# Sensor_MQ-135.net
KiCad netlist of a schematic drawn in Altium Designer
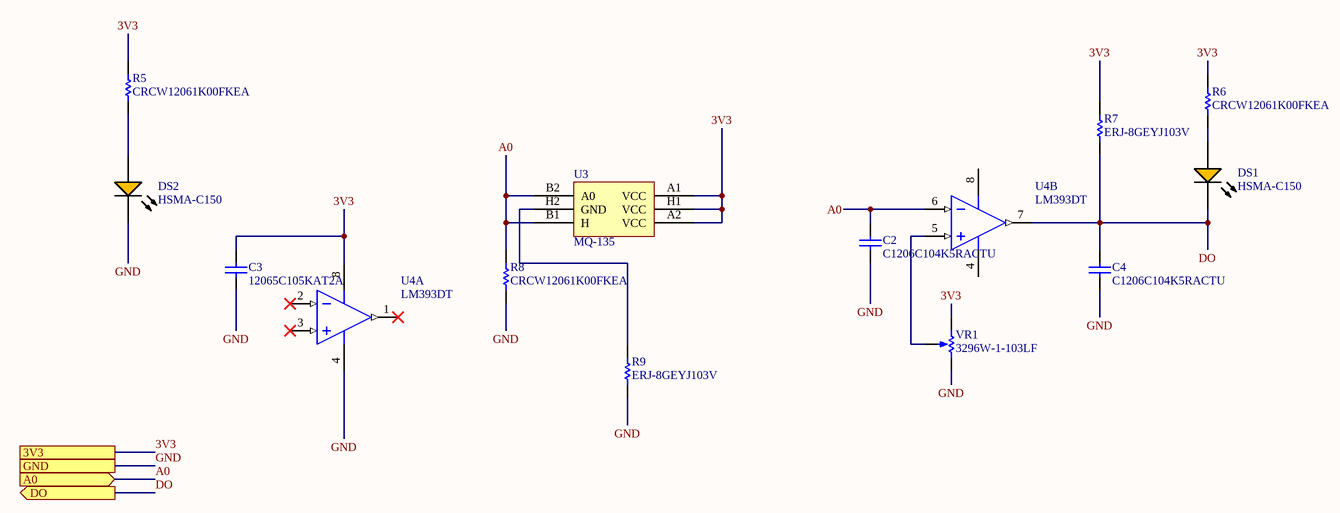
[diagram p0: Sensor_MQ-135.SchDoc]

(export (version "E")
  (design (tool "Eeschema 10.0.6"))
  (components
    (comp (ref "C2")
      (value "C1206C104K5RACTU")
      (footprint "KEMT-1206-2_M")
      (description "CAP, Ceramic, 0.1 uF, +/- 10%, 50 V, -55 to 125 degC, 1206 (3216 Metric), RoHS, Tape and Reel")
      (fields (field (name "MANUFACTURER") "Kemet"))
      (libsource (lib "Altium Content Vault") (part "CAP-NP-2"))
    )
    (comp (ref "C3")
      (value "12065C105KAT2A")
      (footprint "CAPC3216X180X50LL20T25")
      (description "Chip Capacitor, 1 uF, +/- 10%, 50 V, -55 to 125 degC, 1206 (3216 Metric), RoHS, Tape and Reel")
      (fields (field (name "MANUFACTURER") "AVX"))
      (libsource (lib "Altium Content Vault") (part "CAP-NP-2"))
    )
    (comp (ref "C4")
      (value "C1206C104K5RACTU")
      (footprint "KEMT-1206-2_M")
      (description "CAP, Ceramic, 0.1 uF, +/- 10%, 50 V, -55 to 125 degC, 1206 (3216 Metric), RoHS, Tape and Reel")
      (fields (field (name "MANUFACTURER") "Kemet"))
      (libsource (lib "Altium Content Vault") (part "CAP-NP-2"))
    )
    (comp (ref "DS1")
      (value "HSMA-C150")
      (footprint "AVAG-HSMX-C150_V")
      (description "High Performance Chip LED, 60 mW, 25 mA, -30 to 85 degC, 2-Pin SMD, RoHS, Tape and Reel")
      (fields (field (name "MANUFACTURER") "AvagoTechnologies"))
      (libsource (lib "Altium Content Vault") (part "LED-AMBER-AK-2"))
    )
    (comp (ref "DS2")
      (value "HSMA-C150")
      (footprint "AVAG-HSMX-C150_V")
      (description "High Performance Chip LED, 60 mW, 25 mA, -30 to 85 degC, 2-Pin SMD, RoHS, Tape and Reel")
      (fields (field (name "MANUFACTURER") "AvagoTechnologies"))
      (libsource (lib "Altium Content Vault") (part "LED-AMBER-AK-2"))
    )
    (comp (ref "R5")
      (value "CRCW12061K00FKEA")
      (footprint "RESC3216X60X45ML15T20")
      (description "Chip Resistor, 1 KOhm, +/- 1%, 0.25 W, -55 to 155 degC, 1206 (3216 Metric), RoHS, Tape and Reel")
      (fields (field (name "MANUFACTURER") "Vishay Semiconductor") (field (name "TOLERANCE") "1%"))
      (libsource (lib "Altium Content Vault") (part "RES-2"))
    )
    (comp (ref "R6")
      (value "CRCW12061K00FKEA")
      (footprint "RESC3216X60X45ML15T20")
      (description "Chip Resistor, 1 KOhm, +/- 1%, 0.25 W, -55 to 155 degC, 1206 (3216 Metric), RoHS, Tape and Reel")
      (fields (field (name "MANUFACTURER") "Vishay Semiconductor") (field (name "TOLERANCE") "1%"))
      (libsource (lib "Altium Content Vault") (part "RES-2"))
    )
    (comp (ref "R7")
      (value "ERJ-8GEYJ103V")
      (footprint "RESC3216X70X50NL05T20")
      (fields (field (name "MANUFACTURER") "Panasonic"))
      (libsource (lib "Altium Content Vault") (part "RES"))
    )
    (comp (ref "R8")
      (value "CRCW12061K00FKEA")
      (footprint "RESC3216X60X45ML15T20")
      (description "Chip Resistor, 1 KOhm, +/- 1%, 0.25 W, -55 to 155 degC, 1206 (3216 Metric), RoHS, Tape and Reel")
      (fields (field (name "MANUFACTURER") "Vishay Semiconductor") (field (name "TOLERANCE") "1%"))
      (libsource (lib "Altium Content Vault") (part "RES-2"))
    )
    (comp (ref "R9")
      (value "ERJ-8GEYJ103V")
      (footprint "RESC3216X70X50NL05T20")
      (fields (field (name "MANUFACTURER") "Panasonic"))
      (libsource (lib "Altium Content Vault") (part "RES"))
    )
    (comp (ref "U3")
      (value "MQ-135")
      (footprint "PCBComponent_1")
      (libsource (lib "librerias_delvalle") (part "MQ-135"))
    )
    (comp (ref "U4")
      (value "LM393DT")
      (footprint "STM-SO-8_D_L")
      (description "Low-Power, Dual-Voltage Comparator, 2 to 36 V, 0 to 70 degC, 8-Pin SOIC (SO), RoHS, Tape and Reel")
      (fields (field (name "MANUFACTURER") "STMicroelectronics"))
      (libsource (lib "Altium Content Vault") (part "STM-LM393-SO8"))
    )
    (comp (ref "VR1")
      (value "3296W-1-103LF")
      (footprint "BOUR-3296W")
      (fields (field (name "TOLERANCE") "1%"))
      (libsource (lib "Altium Content Vault") (part "RES-POT-3"))
    )
  )
  (nets
    (net (code "1") (name "/3V3") (class "Default")
      (node (ref "C3") (pin "2") (pinfunction "2_2") (pintype "passive"))
      (node (ref "R5") (pin "2") (pinfunction "2_2") (pintype "passive"))
      (node (ref "R6") (pin "2") (pinfunction "2_2") (pintype "passive"))
      (node (ref "R7") (pin "2") (pinfunction "2_2") (pintype "passive"))
      (node (ref "U3") (pin "A1") (pinfunction "VCC_A1") (pintype "power_in"))
      (node (ref "U3") (pin "A2") (pinfunction "VCC_A2") (pintype "power_in"))
      (node (ref "U3") (pin "H1") (pinfunction "VCC_H1") (pintype "power_in"))
      (node (ref "U4") (pin "8") (pinfunction "VCC+_8") (pintype "power_in"))
      (node (ref "VR1") (pin "1") (pinfunction "CCW_1") (pintype "passive"))
    )
    (net (code "2") (name "/A0") (class "Default")
      (node (ref "C2") (pin "2") (pinfunction "2_2") (pintype "passive"))
      (node (ref "R8") (pin "2") (pinfunction "2_2") (pintype "passive"))
      (node (ref "U3") (pin "B1") (pinfunction "H_B1") (pintype "passive"))
      (node (ref "U3") (pin "B2") (pinfunction "A0_B2") (pintype "passive"))
      (node (ref "U4") (pin "6") (pinfunction "IN2-_6") (pintype "input"))
    )
    (net (code "3") (name "/DO") (class "Default")
      (node (ref "C4") (pin "2") (pinfunction "2_2") (pintype "passive"))
      (node (ref "DS1") (pin "2") (pinfunction "K_2") (pintype "passive"))
      (node (ref "R7") (pin "1") (pinfunction "1_1") (pintype "passive"))
      (node (ref "U4") (pin "7") (pinfunction "OUT2_7") (pintype "output"))
    )
    (net (code "4") (name "/GND") (class "Default")
      (node (ref "C2") (pin "1") (pinfunction "1_1") (pintype "passive"))
      (node (ref "C3") (pin "1") (pinfunction "1_1") (pintype "passive"))
      (node (ref "C4") (pin "1") (pinfunction "1_1") (pintype "passive"))
      (node (ref "DS2") (pin "2") (pinfunction "K_2") (pintype "passive"))
      (node (ref "R8") (pin "1") (pinfunction "1_1") (pintype "passive"))
      (node (ref "R9") (pin "1") (pinfunction "1_1") (pintype "passive"))
      (node (ref "U4") (pin "4") (pinfunction "VCC-_4") (pintype "power_in"))
      (node (ref "VR1") (pin "3") (pinfunction "CW_3") (pintype "passive"))
    )
    (net (code "5") (name "Net-(DS1-A)") (class "Default")
      (node (ref "DS1") (pin "1") (pinfunction "A_1") (pintype "passive"))
      (node (ref "R6") (pin "1") (pinfunction "1_1") (pintype "passive"))
    )
    (net (code "6") (name "Net-(DS2-A)") (class "Default")
      (node (ref "DS2") (pin "1") (pinfunction "A_1") (pintype "passive"))
      (node (ref "R5") (pin "1") (pinfunction "1_1") (pintype "passive"))
    )
    (net (code "7") (name "Net-(U3-GND)") (class "Default")
      (node (ref "R9") (pin "2") (pinfunction "2_2") (pintype "passive"))
      (node (ref "U3") (pin "H2") (pinfunction "GND_H2") (pintype "passive"))
    )
    (net (code "8") (name "Net-(U4B-IN2+)") (class "Default")
      (node (ref "U4") (pin "5") (pinfunction "IN2+_5") (pintype "input"))
      (node (ref "VR1") (pin "2") (pinfunction "S_2") (pintype "passive"))
    )
    (net (code "9") (name "unconnected-(U4A-IN1+-Pad3)") (class "Default")
      (node (ref "U4") (pin "3") (pinfunction "IN1+_3") (pintype "input+no_connect"))
    )
    (net (code "10") (name "unconnected-(U4A-IN1--Pad2)") (class "Default")
      (node (ref "U4") (pin "2") (pinfunction "IN1-_2") (pintype "input+no_connect"))
    )
    (net (code "11") (name "unconnected-(U4A-OUT1-Pad1)") (class "Default")
      (node (ref "U4") (pin "1") (pinfunction "OUT1_1") (pintype "output+no_connect"))
    )
    (net (code "12") (name "unconnected-(U4B-VCC+-Pad8)") (class "Default")
      (node (ref "U4") (pin "8") (pinfunction "VCC+_8") (pintype "power_in"))
    )
    (net (code "13") (name "unconnected-(U4B-VCC--Pad4)") (class "Default")
      (node (ref "U4") (pin "4") (pinfunction "VCC-_4") (pintype "power_in"))
    )
  )
)
